# X13_Power_Distribution_D.net
KiCad netlist of a schematic drawn in EAGLE
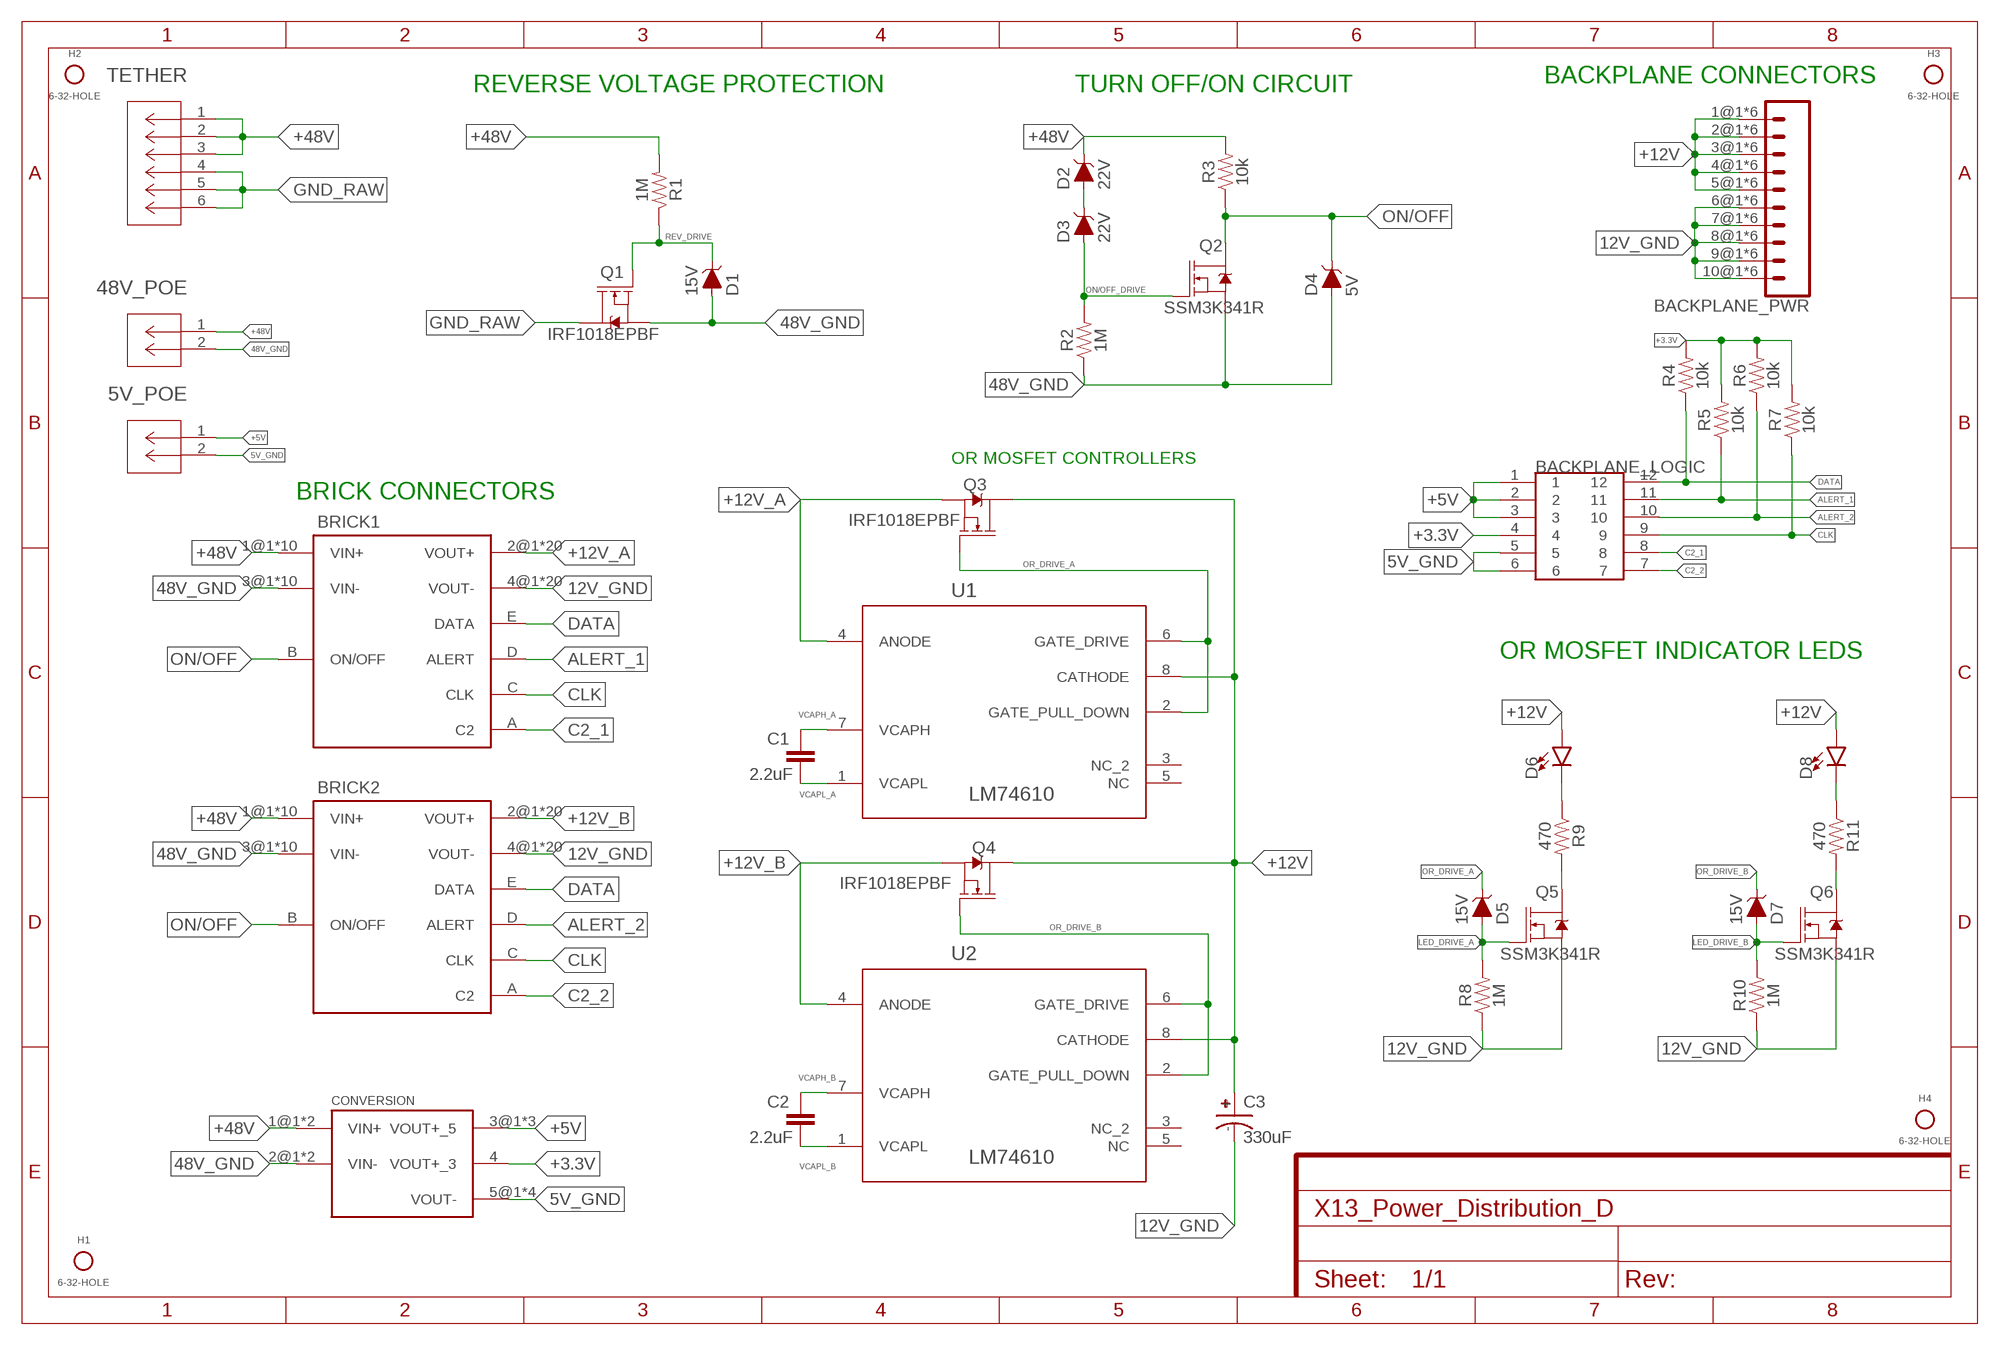
[diagram p0: schematic, sheet 1, part 1 of 2]
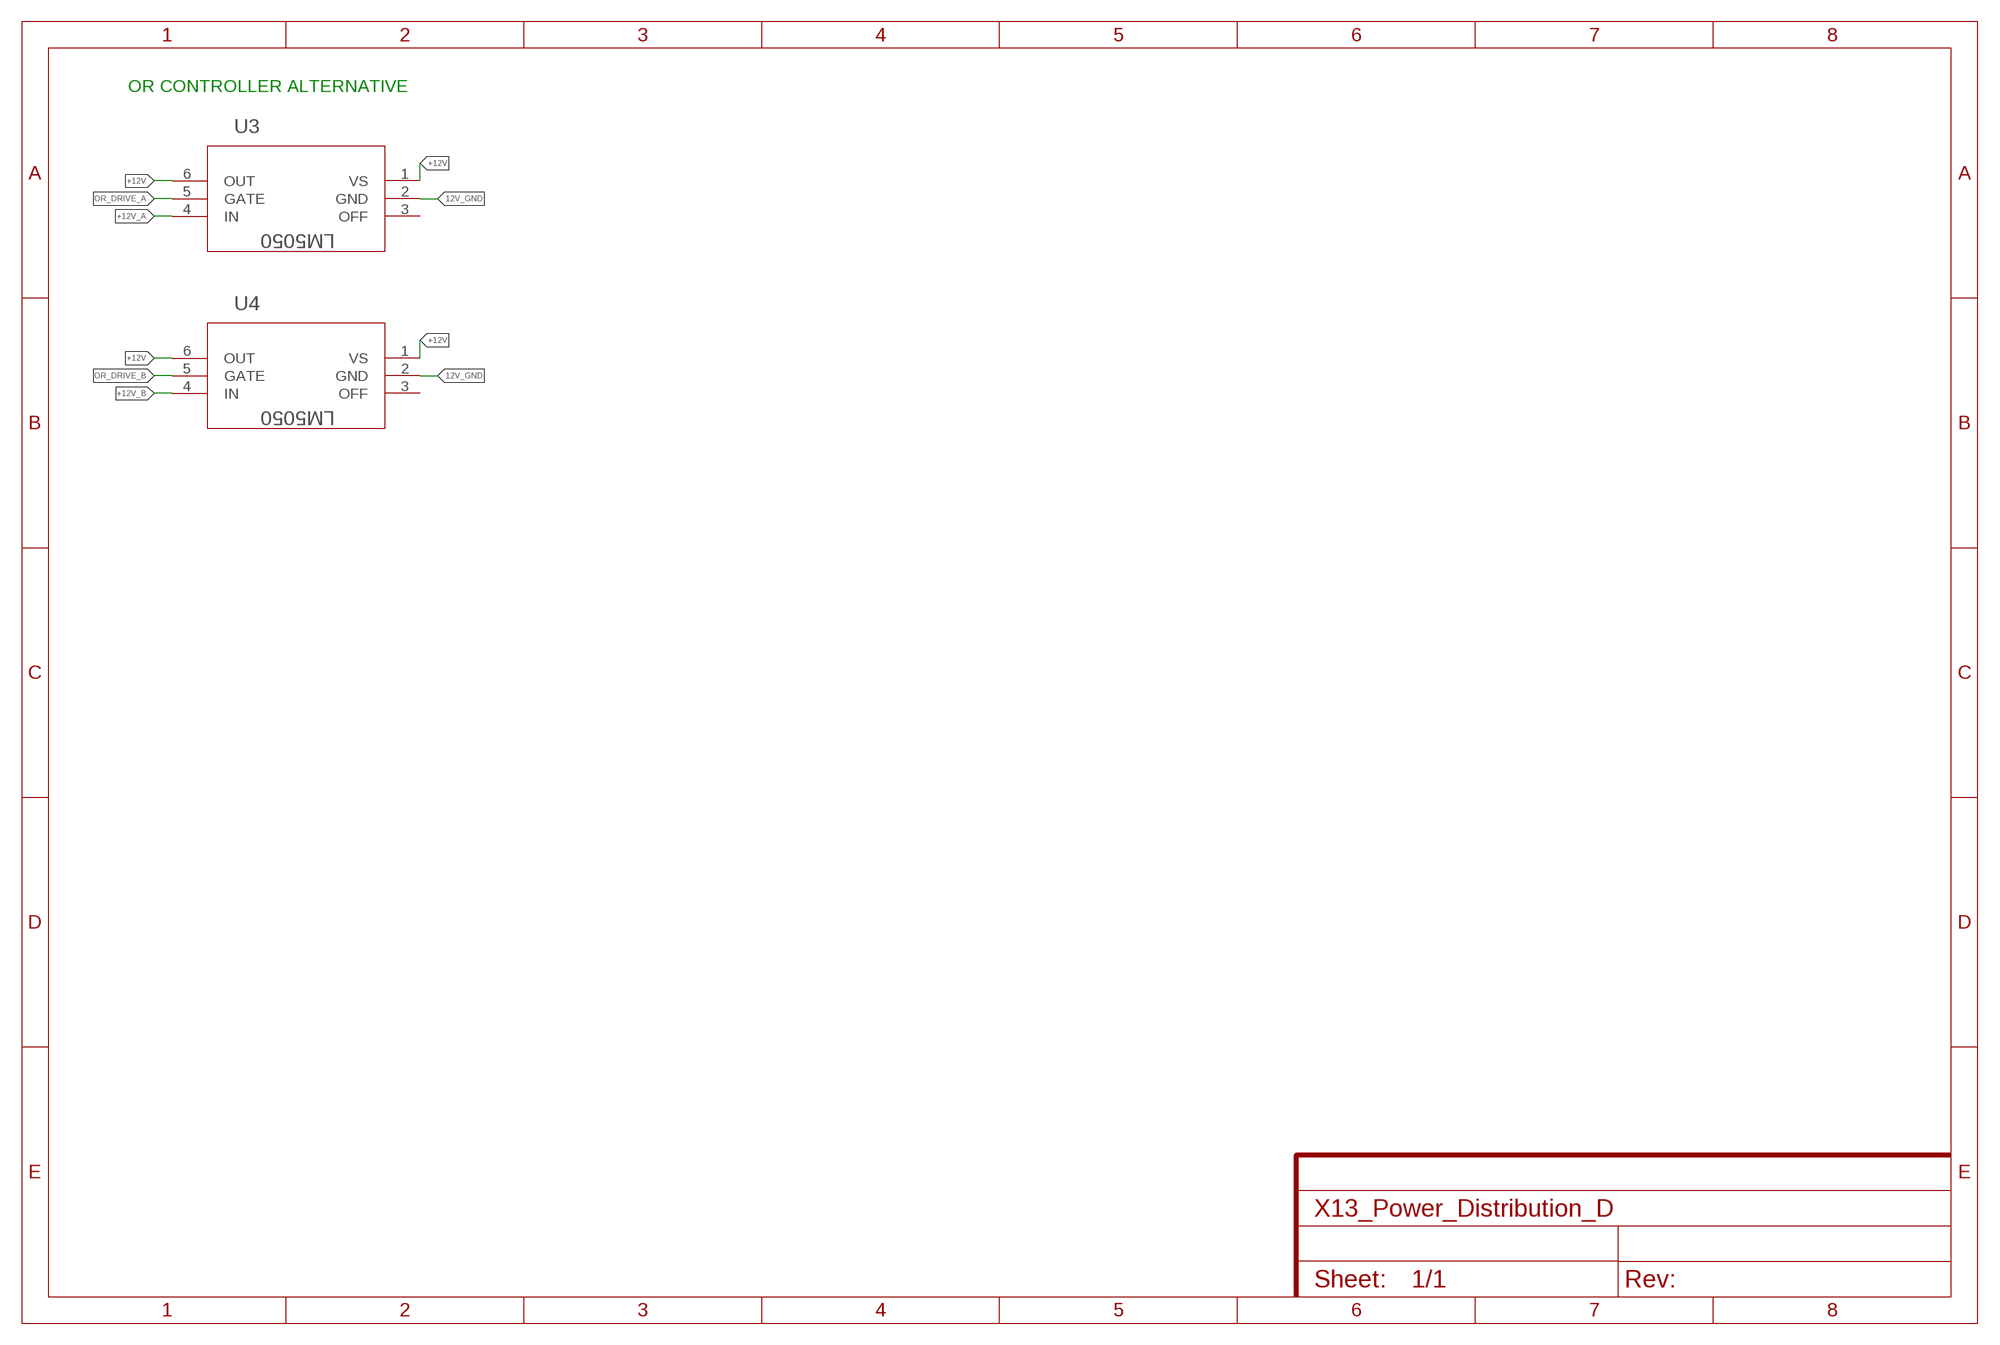
[diagram p1: schematic, sheet 1, part 2 of 2]

(export (version "E")
  (design (tool "Eeschema 10.0.6"))
  (components
    (comp (ref "5V_POE")
      (value "POE_TERMINAL")
      (footprint "eagle-import:CONN2_282834-2_TEC")
      (fields
        (field (name "MANUFACTURER_PART_NUMBER") "282834-2")
        (field (name "COPYRIGHT") "Copyright (C) 2016 Accelerated Designs. All rights reserved")
      )
      (libsource (lib "eagle-import") (part "POE_TERMINAL"))
    )
    (comp (ref "48V_POE")
      (value "POE_TERMINAL")
      (footprint "eagle-import:CONN2_282834-2_TEC")
      (fields
        (field (name "MANUFACTURER_PART_NUMBER") "282834-2")
        (field (name "COPYRIGHT") "Copyright (C) 2016 Accelerated Designs. All rights reserved")
      )
      (libsource (lib "eagle-import") (part "POE_TERMINAL"))
    )
    (comp (ref "BACKPLANE_LOGIC")
      (value "IPL1-106-01-L-D-K")
      (footprint "eagle-import:IPL1-106-01-L-D-K")
      (libsource (lib "eagle-import") (part "IPL1-106-01-L-D-K"))
    )
    (comp (ref "BACKPLANE_PWR")
      (value "MPPT-10-01-01-L-RA-SD")
      (footprint "eagle-import:MPPT-10-01-01-L-RA-SD")
      (libsource (lib "eagle-import") (part "MPPT-10-01-01-L-RA-SD"))
    )
    (comp (ref "BRICK1")
      (value "DIST2BRICKVER_D2")
      (footprint "eagle-import:DIST2BRICK_D2")
      (libsource (lib "eagle-import") (part "DIST2BRICKVER_D2"))
    )
    (comp (ref "BRICK2")
      (value "DIST2BRICKVER_D2")
      (footprint "eagle-import:DIST2BRICK_D2")
      (libsource (lib "eagle-import") (part "DIST2BRICKVER_D2"))
    )
    (comp (ref "C1")
      (value "2.2uF")
      (footprint "eagle-import:0603")
      (libsource (lib "eagle-import") (part "0.1UF-0603-100V-10%"))
    )
    (comp (ref "C2")
      (value "2.2uF")
      (footprint "eagle-import:0603")
      (libsource (lib "eagle-import") (part "0.1UF-0603-100V-10%"))
    )
    (comp (ref "C3")
      (value "330uF")
      (footprint "eagle-import:CAPAE1030X1050N")
      (fields
        (field (name "ARROW_PART_NUMBER") "UCM1H331MNL1GS")
        (field (name "MOUSER_PART_NUMBER") "647-UCM1H331MNL1GS")
      )
      (libsource (lib "eagle-import") (part "UCM1H331MNL1GS"))
    )
    (comp (ref "CONVERSION")
      (value "DIST2CON")
      (footprint "eagle-import:DIST2CON")
      (libsource (lib "eagle-import") (part "DIST2CON"))
    )
    (comp (ref "D1")
      (value "15V")
      (footprint "eagle-import:SOD-323")
      (libsource (lib "eagle-import") (part "DIODE-ZENER-BZT52C3V6S"))
    )
    (comp (ref "D2")
      (value "22V")
      (footprint "eagle-import:SOD-323")
      (libsource (lib "eagle-import") (part "DIODE-ZENER-BZT52C3V6S"))
    )
    (comp (ref "D3")
      (value "22V")
      (footprint "eagle-import:SOD-323")
      (libsource (lib "eagle-import") (part "DIODE-ZENER-BZT52C3V6S"))
    )
    (comp (ref "D4")
      (value "5V")
      (footprint "eagle-import:SOD-323")
      (libsource (lib "eagle-import") (part "DIODE-ZENER-BZT52C3V6S"))
    )
    (comp (ref "D5")
      (value "15V")
      (footprint "eagle-import:SOD-323")
      (libsource (lib "eagle-import") (part "DIODE-ZENER-BZT52C3V6S"))
    )
    (comp (ref "D6")
      (value "LED0603")
      (footprint "eagle-import:LED-0603")
      (libsource (lib "eagle-import") (part "LED0603"))
    )
    (comp (ref "D7")
      (value "15V")
      (footprint "eagle-import:SOD-323")
      (libsource (lib "eagle-import") (part "DIODE-ZENER-BZT52C3V6S"))
    )
    (comp (ref "D8")
      (value "LED0603")
      (footprint "eagle-import:LED-0603")
      (libsource (lib "eagle-import") (part "LED0603"))
    )
    (comp (ref "H1")
      (value "6-32-HOLE")
      (footprint "eagle-import:6-32-HOLE")
      (libsource (lib "eagle-import") (part "6-32-HOLE"))
    )
    (comp (ref "H2")
      (value "6-32-HOLE")
      (footprint "eagle-import:6-32-HOLE")
      (libsource (lib "eagle-import") (part "6-32-HOLE"))
    )
    (comp (ref "H3")
      (value "6-32-HOLE")
      (footprint "eagle-import:6-32-HOLE")
      (libsource (lib "eagle-import") (part "6-32-HOLE"))
    )
    (comp (ref "H4")
      (value "6-32-HOLE")
      (footprint "eagle-import:6-32-HOLE")
      (libsource (lib "eagle-import") (part "6-32-HOLE"))
    )
    (comp (ref "Q1")
      (value "IRF1018EPBF")
      (footprint "eagle-import:TO263")
      (libsource (lib "eagle-import") (part "IRF1018EPBF"))
    )
    (comp (ref "Q2")
      (value "SSM3K341R")
      (footprint "eagle-import:SOT323")
      (libsource (lib "eagle-import") (part "MOSFET-NCH-2N7002PW"))
    )
    (comp (ref "Q3")
      (value "IRF1018EPBF")
      (footprint "eagle-import:TO263")
      (libsource (lib "eagle-import") (part "IRF1018EPBF"))
    )
    (comp (ref "Q4")
      (value "IRF1018EPBF")
      (footprint "eagle-import:TO263")
      (libsource (lib "eagle-import") (part "IRF1018EPBF"))
    )
    (comp (ref "Q5")
      (value "SSM3K341R")
      (footprint "eagle-import:SOT323")
      (libsource (lib "eagle-import") (part "MOSFET-NCH-2N7002PW"))
    )
    (comp (ref "Q6")
      (value "SSM3K341R")
      (footprint "eagle-import:SOT323")
      (libsource (lib "eagle-import") (part "MOSFET-NCH-2N7002PW"))
    )
    (comp (ref "R1")
      (value "1M")
      (footprint "eagle-import:0603")
      (libsource (lib "eagle-import") (part "RESISTOR0603"))
    )
    (comp (ref "R2")
      (value "1M")
      (footprint "eagle-import:0603")
      (fields (field (name "SPICEPREFIX") "R"))
      (libsource (lib "eagle-import") (part "RESISTOR0603"))
    )
    (comp (ref "R3")
      (value "10k")
      (footprint "eagle-import:0603")
      (fields (field (name "SPICEPREFIX") "R"))
      (libsource (lib "eagle-import") (part "RESISTOR0603"))
    )
    (comp (ref "R4")
      (value "10k")
      (footprint "eagle-import:0603")
      (libsource (lib "eagle-import") (part "RESISTOR0603"))
    )
    (comp (ref "R5")
      (value "10k")
      (footprint "eagle-import:0603")
      (libsource (lib "eagle-import") (part "RESISTOR0603"))
    )
    (comp (ref "R6")
      (value "10k")
      (footprint "eagle-import:0603")
      (libsource (lib "eagle-import") (part "RESISTOR0603"))
    )
    (comp (ref "R7")
      (value "10k")
      (footprint "eagle-import:0603")
      (libsource (lib "eagle-import") (part "RESISTOR0603"))
    )
    (comp (ref "R8")
      (value "1M")
      (footprint "eagle-import:0603")
      (fields (field (name "SPICEPREFIX") "R"))
      (libsource (lib "eagle-import") (part "RESISTOR0603"))
    )
    (comp (ref "R9")
      (value "470")
      (footprint "eagle-import:0603")
      (libsource (lib "eagle-import") (part "RESISTOR0603"))
    )
    (comp (ref "R10")
      (value "1M")
      (footprint "eagle-import:0603")
      (fields (field (name "SPICEPREFIX") "R"))
      (libsource (lib "eagle-import") (part "RESISTOR0603"))
    )
    (comp (ref "R11")
      (value "470")
      (footprint "eagle-import:0603")
      (libsource (lib "eagle-import") (part "RESISTOR0603"))
    )
    (comp (ref "TETHER")
      (value "48V")
      (footprint "eagle-import:CON6_P5MM_VER_TERM-BLK_TYC")
      (fields (field (name "MANUFACTURER_PART_NUMBER") "796636-6"))
      (libsource (lib "eagle-import") (part "DIST_TO_TETHER"))
    )
    (comp (ref "U1")
      (value "LM74610")
      (footprint "eagle-import:DGK0008A_M")
      (fields (field (name "MANUFACTURER") "Texas Instruments") (field (name "PARTNUMBER") "LM74610QDGKRQ1"))
      (libsource (lib "eagle-import") (part "DIST_OR_DIODEDGK0008A_M"))
    )
    (comp (ref "U2")
      (value "LM74610")
      (footprint "eagle-import:DGK0008A_M")
      (fields (field (name "MANUFACTURER") "Texas Instruments") (field (name "PARTNUMBER") "LM74610QDGKRQ1"))
      (libsource (lib "eagle-import") (part "DIST_OR_DIODEDGK0008A_M"))
    )
    (comp (ref "U3")
      (value "LM5050")
      (footprint "eagle-import:MK06A-M")
      (fields
        (field (name "MANUFACTURER") "Texas Instruments")
        (field (name "MANUFACTURER_PART_NUMBER") "LM5050MK-1/NOPB")
      )
      (libsource (lib "eagle-import") (part "DIST_OR_CONTROL_ALTMK06A-M"))
    )
    (comp (ref "U4")
      (value "LM5050")
      (footprint "eagle-import:MK06A-M")
      (fields
        (field (name "MANUFACTURER") "Texas Instruments")
        (field (name "MANUFACTURER_PART_NUMBER") "LM5050MK-1/NOPB")
      )
      (libsource (lib "eagle-import") (part "DIST_OR_CONTROL_ALTMK06A-M"))
    )
  )
  (nets
    (net (code "1") (name "+3.3V") (class "Default")
      (node (ref "BACKPLANE_LOGIC") (pin "4") (pinfunction "4_4") (pintype "bidirectional"))
      (node (ref "CONVERSION") (pin "4") (pinfunction "VOUT+_3_4") (pintype "bidirectional"))
      (node (ref "R4") (pin "2") (pinfunction "2_2") (pintype "passive"))
      (node (ref "R5") (pin "2") (pinfunction "2_2") (pintype "passive"))
      (node (ref "R6") (pin "2") (pinfunction "2_2") (pintype "passive"))
      (node (ref "R7") (pin "2") (pinfunction "2_2") (pintype "passive"))
    )
    (net (code "2") (name "+5V") (class "Default")
      (node (ref "5V_POE") (pin "1") (pinfunction "1_1") (pintype "passive"))
      (node (ref "BACKPLANE_LOGIC") (pin "1") (pinfunction "1_1") (pintype "bidirectional"))
      (node (ref "BACKPLANE_LOGIC") (pin "2") (pinfunction "2_2") (pintype "bidirectional"))
      (node (ref "BACKPLANE_LOGIC") (pin "3") (pinfunction "3_3") (pintype "bidirectional"))
      (node (ref "CONVERSION") (pin "3@1") (pinfunction "VOUT+_5_3@1") (pintype "bidirectional"))
      (node (ref "CONVERSION") (pin "3@2") (pinfunction "VOUT+_5_3@2") (pintype "bidirectional"))
      (node (ref "CONVERSION") (pin "3@3") (pinfunction "VOUT+_5_3@3") (pintype "bidirectional"))
    )
    (net (code "3") (name "+12V") (class "Default")
      (node (ref "BACKPLANE_PWR") (pin "1@1") (pinfunction "1_1@1") (pintype "passive"))
      (node (ref "BACKPLANE_PWR") (pin "1@2") (pinfunction "1_1@2") (pintype "passive"))
      (node (ref "BACKPLANE_PWR") (pin "1@3") (pinfunction "1_1@3") (pintype "passive"))
      (node (ref "BACKPLANE_PWR") (pin "1@4") (pinfunction "1_1@4") (pintype "passive"))
      (node (ref "BACKPLANE_PWR") (pin "1@5") (pinfunction "1_1@5") (pintype "passive"))
      (node (ref "BACKPLANE_PWR") (pin "1@6") (pinfunction "1_1@6") (pintype "passive"))
      (node (ref "BACKPLANE_PWR") (pin "2@1") (pinfunction "2_2@1") (pintype "passive"))
      (node (ref "BACKPLANE_PWR") (pin "2@2") (pinfunction "2_2@2") (pintype "passive"))
      (node (ref "BACKPLANE_PWR") (pin "2@3") (pinfunction "2_2@3") (pintype "passive"))
      (node (ref "BACKPLANE_PWR") (pin "2@4") (pinfunction "2_2@4") (pintype "passive"))
      (node (ref "BACKPLANE_PWR") (pin "2@5") (pinfunction "2_2@5") (pintype "passive"))
      (node (ref "BACKPLANE_PWR") (pin "2@6") (pinfunction "2_2@6") (pintype "passive"))
      (node (ref "BACKPLANE_PWR") (pin "3@1") (pinfunction "3_3@1") (pintype "passive"))
      (node (ref "BACKPLANE_PWR") (pin "3@2") (pinfunction "3_3@2") (pintype "passive"))
      (node (ref "BACKPLANE_PWR") (pin "3@3") (pinfunction "3_3@3") (pintype "passive"))
      (node (ref "BACKPLANE_PWR") (pin "3@4") (pinfunction "3_3@4") (pintype "passive"))
      (node (ref "BACKPLANE_PWR") (pin "3@5") (pinfunction "3_3@5") (pintype "passive"))
      (node (ref "BACKPLANE_PWR") (pin "3@6") (pinfunction "3_3@6") (pintype "passive"))
      (node (ref "BACKPLANE_PWR") (pin "4@1") (pinfunction "4_4@1") (pintype "passive"))
      (node (ref "BACKPLANE_PWR") (pin "4@2") (pinfunction "4_4@2") (pintype "passive"))
      (node (ref "BACKPLANE_PWR") (pin "4@3") (pinfunction "4_4@3") (pintype "passive"))
      (node (ref "BACKPLANE_PWR") (pin "4@4") (pinfunction "4_4@4") (pintype "passive"))
      (node (ref "BACKPLANE_PWR") (pin "4@5") (pinfunction "4_4@5") (pintype "passive"))
      (node (ref "BACKPLANE_PWR") (pin "4@6") (pinfunction "4_4@6") (pintype "passive"))
      (node (ref "BACKPLANE_PWR") (pin "5@1") (pinfunction "5_5@1") (pintype "passive"))
      (node (ref "BACKPLANE_PWR") (pin "5@2") (pinfunction "5_5@2") (pintype "passive"))
      (node (ref "BACKPLANE_PWR") (pin "5@3") (pinfunction "5_5@3") (pintype "passive"))
      (node (ref "BACKPLANE_PWR") (pin "5@4") (pinfunction "5_5@4") (pintype "passive"))
      (node (ref "BACKPLANE_PWR") (pin "5@5") (pinfunction "5_5@5") (pintype "passive"))
      (node (ref "BACKPLANE_PWR") (pin "5@6") (pinfunction "5_5@6") (pintype "passive"))
      (node (ref "C3") (pin "+") (pinfunction "+_+") (pintype "bidirectional"))
      (node (ref "D6") (pin "A") (pinfunction "A_A") (pintype "passive"))
      (node (ref "D8") (pin "A") (pinfunction "A_A") (pintype "passive"))
      (node (ref "Q3") (pin "3") (pinfunction "D_3") (pintype "bidirectional"))
      (node (ref "Q4") (pin "3") (pinfunction "D_3") (pintype "bidirectional"))
      (node (ref "U1") (pin "8") (pinfunction "CATHODE_8") (pintype "output"))
      (node (ref "U2") (pin "8") (pinfunction "CATHODE_8") (pintype "output"))
      (node (ref "U3") (pin "1") (pinfunction "VS_1") (pintype "passive"))
      (node (ref "U3") (pin "6") (pinfunction "OUT_6") (pintype "output"))
      (node (ref "U4") (pin "1") (pinfunction "VS_1") (pintype "passive"))
      (node (ref "U4") (pin "6") (pinfunction "OUT_6") (pintype "output"))
    )
    (net (code "4") (name "+12V_A") (class "Default")
      (node (ref "BRICK1") (pin "2@1") (pinfunction "VOUT+_2@1") (pintype "bidirectional"))
      (node (ref "BRICK1") (pin "2@10") (pinfunction "VOUT+_2@10") (pintype "bidirectional"))
      (node (ref "BRICK1") (pin "2@11") (pinfunction "VOUT+_2@11") (pintype "bidirectional"))
      (node (ref "BRICK1") (pin "2@12") (pinfunction "VOUT+_2@12") (pintype "bidirectional"))
      (node (ref "BRICK1") (pin "2@13") (pinfunction "VOUT+_2@13") (pintype "bidirectional"))
      (node (ref "BRICK1") (pin "2@14") (pinfunction "VOUT+_2@14") (pintype "bidirectional"))
      (node (ref "BRICK1") (pin "2@15") (pinfunction "VOUT+_2@15") (pintype "bidirectional"))
      (node (ref "BRICK1") (pin "2@16") (pinfunction "VOUT+_2@16") (pintype "bidirectional"))
      (node (ref "BRICK1") (pin "2@17") (pinfunction "VOUT+_2@17") (pintype "bidirectional"))
      (node (ref "BRICK1") (pin "2@18") (pinfunction "VOUT+_2@18") (pintype "bidirectional"))
      (node (ref "BRICK1") (pin "2@19") (pinfunction "VOUT+_2@19") (pintype "bidirectional"))
      (node (ref "BRICK1") (pin "2@2") (pinfunction "VOUT+_2@2") (pintype "bidirectional"))
      (node (ref "BRICK1") (pin "2@20") (pinfunction "VOUT+_2@20") (pintype "bidirectional"))
      (node (ref "BRICK1") (pin "2@3") (pinfunction "VOUT+_2@3") (pintype "bidirectional"))
      (node (ref "BRICK1") (pin "2@4") (pinfunction "VOUT+_2@4") (pintype "bidirectional"))
      (node (ref "BRICK1") (pin "2@5") (pinfunction "VOUT+_2@5") (pintype "bidirectional"))
      (node (ref "BRICK1") (pin "2@6") (pinfunction "VOUT+_2@6") (pintype "bidirectional"))
      (node (ref "BRICK1") (pin "2@7") (pinfunction "VOUT+_2@7") (pintype "bidirectional"))
      (node (ref "BRICK1") (pin "2@8") (pinfunction "VOUT+_2@8") (pintype "bidirectional"))
      (node (ref "BRICK1") (pin "2@9") (pinfunction "VOUT+_2@9") (pintype "bidirectional"))
      (node (ref "Q3") (pin "2") (pinfunction "S_2") (pintype "bidirectional"))
      (node (ref "U1") (pin "4") (pinfunction "ANODE_4") (pintype "power_in"))
      (node (ref "U3") (pin "4") (pinfunction "IN_4") (pintype "input"))
    )
    (net (code "5") (name "+12V_B") (class "Default")
      (node (ref "BRICK2") (pin "2@1") (pinfunction "VOUT+_2@1") (pintype "bidirectional"))
      (node (ref "BRICK2") (pin "2@10") (pinfunction "VOUT+_2@10") (pintype "bidirectional"))
      (node (ref "BRICK2") (pin "2@11") (pinfunction "VOUT+_2@11") (pintype "bidirectional"))
      (node (ref "BRICK2") (pin "2@12") (pinfunction "VOUT+_2@12") (pintype "bidirectional"))
      (node (ref "BRICK2") (pin "2@13") (pinfunction "VOUT+_2@13") (pintype "bidirectional"))
      (node (ref "BRICK2") (pin "2@14") (pinfunction "VOUT+_2@14") (pintype "bidirectional"))
      (node (ref "BRICK2") (pin "2@15") (pinfunction "VOUT+_2@15") (pintype "bidirectional"))
      (node (ref "BRICK2") (pin "2@16") (pinfunction "VOUT+_2@16") (pintype "bidirectional"))
      (node (ref "BRICK2") (pin "2@17") (pinfunction "VOUT+_2@17") (pintype "bidirectional"))
      (node (ref "BRICK2") (pin "2@18") (pinfunction "VOUT+_2@18") (pintype "bidirectional"))
      (node (ref "BRICK2") (pin "2@19") (pinfunction "VOUT+_2@19") (pintype "bidirectional"))
      (node (ref "BRICK2") (pin "2@2") (pinfunction "VOUT+_2@2") (pintype "bidirectional"))
      (node (ref "BRICK2") (pin "2@20") (pinfunction "VOUT+_2@20") (pintype "bidirectional"))
      (node (ref "BRICK2") (pin "2@3") (pinfunction "VOUT+_2@3") (pintype "bidirectional"))
      (node (ref "BRICK2") (pin "2@4") (pinfunction "VOUT+_2@4") (pintype "bidirectional"))
      (node (ref "BRICK2") (pin "2@5") (pinfunction "VOUT+_2@5") (pintype "bidirectional"))
      (node (ref "BRICK2") (pin "2@6") (pinfunction "VOUT+_2@6") (pintype "bidirectional"))
      (node (ref "BRICK2") (pin "2@7") (pinfunction "VOUT+_2@7") (pintype "bidirectional"))
      (node (ref "BRICK2") (pin "2@8") (pinfunction "VOUT+_2@8") (pintype "bidirectional"))
      (node (ref "BRICK2") (pin "2@9") (pinfunction "VOUT+_2@9") (pintype "bidirectional"))
      (node (ref "Q4") (pin "2") (pinfunction "S_2") (pintype "bidirectional"))
      (node (ref "U2") (pin "4") (pinfunction "ANODE_4") (pintype "power_in"))
      (node (ref "U4") (pin "4") (pinfunction "IN_4") (pintype "input"))
    )
    (net (code "6") (name "+48V") (class "Default")
      (node (ref "48V_POE") (pin "1") (pinfunction "1_1") (pintype "passive"))
      (node (ref "BRICK1") (pin "1@1") (pinfunction "VIN+_1@1") (pintype "bidirectional"))
      (node (ref "BRICK1") (pin "1@10") (pinfunction "VIN+_1@10") (pintype "bidirectional"))
      (node (ref "BRICK1") (pin "1@2") (pinfunction "VIN+_1@2") (pintype "bidirectional"))
      (node (ref "BRICK1") (pin "1@3") (pinfunction "VIN+_1@3") (pintype "bidirectional"))
      (node (ref "BRICK1") (pin "1@4") (pinfunction "VIN+_1@4") (pintype "bidirectional"))
      (node (ref "BRICK1") (pin "1@5") (pinfunction "VIN+_1@5") (pintype "bidirectional"))
      (node (ref "BRICK1") (pin "1@6") (pinfunction "VIN+_1@6") (pintype "bidirectional"))
      (node (ref "BRICK1") (pin "1@7") (pinfunction "VIN+_1@7") (pintype "bidirectional"))
      (node (ref "BRICK1") (pin "1@8") (pinfunction "VIN+_1@8") (pintype "bidirectional"))
      (node (ref "BRICK1") (pin "1@9") (pinfunction "VIN+_1@9") (pintype "bidirectional"))
      (node (ref "BRICK2") (pin "1@1") (pinfunction "VIN+_1@1") (pintype "bidirectional"))
      (node (ref "BRICK2") (pin "1@10") (pinfunction "VIN+_1@10") (pintype "bidirectional"))
      (node (ref "BRICK2") (pin "1@2") (pinfunction "VIN+_1@2") (pintype "bidirectional"))
      (node (ref "BRICK2") (pin "1@3") (pinfunction "VIN+_1@3") (pintype "bidirectional"))
      (node (ref "BRICK2") (pin "1@4") (pinfunction "VIN+_1@4") (pintype "bidirectional"))
      (node (ref "BRICK2") (pin "1@5") (pinfunction "VIN+_1@5") (pintype "bidirectional"))
      (node (ref "BRICK2") (pin "1@6") (pinfunction "VIN+_1@6") (pintype "bidirectional"))
      (node (ref "BRICK2") (pin "1@7") (pinfunction "VIN+_1@7") (pintype "bidirectional"))
      (node (ref "BRICK2") (pin "1@8") (pinfunction "VIN+_1@8") (pintype "bidirectional"))
      (node (ref "BRICK2") (pin "1@9") (pinfunction "VIN+_1@9") (pintype "bidirectional"))
      (node (ref "CONVERSION") (pin "1@1") (pinfunction "VIN+_1@1") (pintype "bidirectional"))
      (node (ref "CONVERSION") (pin "1@2") (pinfunction "VIN+_1@2") (pintype "bidirectional"))
      (node (ref "D2") (pin "C") (pinfunction "C_C") (pintype "passive"))
      (node (ref "R1") (pin "2") (pinfunction "2_2") (pintype "passive"))
      (node (ref "R3") (pin "2") (pinfunction "2_2") (pintype "passive"))
      (node (ref "TETHER") (pin "1") (pinfunction "1_1") (pintype "passive"))
      (node (ref "TETHER") (pin "2") (pinfunction "2_2") (pintype "passive"))
      (node (ref "TETHER") (pin "3") (pinfunction "3_3") (pintype "passive"))
    )
    (net (code "7") (name "/ON{slash}OFF_DRIVE") (class "Default")
      (node (ref "D3") (pin "A") (pinfunction "A_A") (pintype "passive"))
      (node (ref "Q2") (pin "1") (pinfunction "G_1") (pintype "bidirectional"))
      (node (ref "R2") (pin "2") (pinfunction "2_2") (pintype "passive"))
    )
    (net (code "8") (name "/REV_DRIVE") (class "Default")
      (node (ref "D1") (pin "C") (pinfunction "C_C") (pintype "passive"))
      (node (ref "Q1") (pin "1") (pinfunction "G_1") (pintype "bidirectional"))
      (node (ref "R1") (pin "1") (pinfunction "1_1") (pintype "passive"))
    )
    (net (code "9") (name "/VCAPH_A") (class "Default")
      (node (ref "C1") (pin "1") (pinfunction "1_1") (pintype "passive"))
      (node (ref "U1") (pin "7") (pinfunction "VCAPH_7") (pintype "passive"))
    )
    (net (code "10") (name "/VCAPH_B") (class "Default")
      (node (ref "C2") (pin "1") (pinfunction "1_1") (pintype "passive"))
      (node (ref "U2") (pin "7") (pinfunction "VCAPH_7") (pintype "passive"))
    )
    (net (code "11") (name "/VCAPL_A") (class "Default")
      (node (ref "C1") (pin "2") (pinfunction "2_2") (pintype "passive"))
      (node (ref "U1") (pin "1") (pinfunction "VCAPL_1") (pintype "passive"))
    )
    (net (code "12") (name "/VCAPL_B") (class "Default")
      (node (ref "C2") (pin "2") (pinfunction "2_2") (pintype "passive"))
      (node (ref "U2") (pin "1") (pinfunction "VCAPL_1") (pintype "passive"))
    )
    (net (code "13") (name "5V_GND") (class "Default")
      (node (ref "5V_POE") (pin "2") (pinfunction "2_2") (pintype "passive"))
      (node (ref "BACKPLANE_LOGIC") (pin "5") (pinfunction "5_5") (pintype "bidirectional"))
      (node (ref "BACKPLANE_LOGIC") (pin "6") (pinfunction "6_6") (pintype "bidirectional"))
      (node (ref "CONVERSION") (pin "5@1") (pinfunction "VOUT-_5@1") (pintype "bidirectional"))
      (node (ref "CONVERSION") (pin "5@2") (pinfunction "VOUT-_5@2") (pintype "bidirectional"))
      (node (ref "CONVERSION") (pin "5@3") (pinfunction "VOUT-_5@3") (pintype "bidirectional"))
      (node (ref "CONVERSION") (pin "5@4") (pinfunction "VOUT-_5@4") (pintype "bidirectional"))
    )
    (net (code "14") (name "12V_GND") (class "Default")
      (node (ref "BACKPLANE_PWR") (pin "10@1") (pinfunction "10_10@1") (pintype "passive"))
      (node (ref "BACKPLANE_PWR") (pin "10@2") (pinfunction "10_10@2") (pintype "passive"))
      (node (ref "BACKPLANE_PWR") (pin "10@3") (pinfunction "10_10@3") (pintype "passive"))
      (node (ref "BACKPLANE_PWR") (pin "10@4") (pinfunction "10_10@4") (pintype "passive"))
      (node (ref "BACKPLANE_PWR") (pin "10@5") (pinfunction "10_10@5") (pintype "passive"))
      (node (ref "BACKPLANE_PWR") (pin "10@6") (pinfunction "10_10@6") (pintype "passive"))
      (node (ref "BACKPLANE_PWR") (pin "6@1") (pinfunction "6_6@1") (pintype "passive"))
      (node (ref "BACKPLANE_PWR") (pin "6@2") (pinfunction "6_6@2") (pintype "passive"))
      (node (ref "BACKPLANE_PWR") (pin "6@3") (pinfunction "6_6@3") (pintype "passive"))
      (node (ref "BACKPLANE_PWR") (pin "6@4") (pinfunction "6_6@4") (pintype "passive"))
      (node (ref "BACKPLANE_PWR") (pin "6@5") (pinfunction "6_6@5") (pintype "passive"))
      (node (ref "BACKPLANE_PWR") (pin "6@6") (pinfunction "6_6@6") (pintype "passive"))
      (node (ref "BACKPLANE_PWR") (pin "7@1") (pinfunction "7_7@1") (pintype "passive"))
      (node (ref "BACKPLANE_PWR") (pin "7@2") (pinfunction "7_7@2") (pintype "passive"))
      (node (ref "BACKPLANE_PWR") (pin "7@3") (pinfunction "7_7@3") (pintype "passive"))
      (node (ref "BACKPLANE_PWR") (pin "7@4") (pinfunction "7_7@4") (pintype "passive"))
      (node (ref "BACKPLANE_PWR") (pin "7@5") (pinfunction "7_7@5") (pintype "passive"))
      (node (ref "BACKPLANE_PWR") (pin "7@6") (pinfunction "7_7@6") (pintype "passive"))
      (node (ref "BACKPLANE_PWR") (pin "8@1") (pinfunction "8_8@1") (pintype "passive"))
      (node (ref "BACKPLANE_PWR") (pin "8@2") (pinfunction "8_8@2") (pintype "passive"))
      (node (ref "BACKPLANE_PWR") (pin "8@3") (pinfunction "8_8@3") (pintype "passive"))
      (node (ref "BACKPLANE_PWR") (pin "8@4") (pinfunction "8_8@4") (pintype "passive"))
      (node (ref "BACKPLANE_PWR") (pin "8@5") (pinfunction "8_8@5") (pintype "passive"))
      (node (ref "BACKPLANE_PWR") (pin "8@6") (pinfunction "8_8@6") (pintype "passive"))
      (node (ref "BACKPLANE_PWR") (pin "9@1") (pinfunction "9_9@1") (pintype "passive"))
      (node (ref "BACKPLANE_PWR") (pin "9@2") (pinfunction "9_9@2") (pintype "passive"))
      (node (ref "BACKPLANE_PWR") (pin "9@3") (pinfunction "9_9@3") (pintype "passive"))
      (node (ref "BACKPLANE_PWR") (pin "9@4") (pinfunction "9_9@4") (pintype "passive"))
      (node (ref "BACKPLANE_PWR") (pin "9@5") (pinfunction "9_9@5") (pintype "passive"))
      (node (ref "BACKPLANE_PWR") (pin "9@6") (pinfunction "9_9@6") (pintype "passive"))
      (node (ref "BRICK1") (pin "4@1") (pinfunction "VOUT-_4@1") (pintype "bidirectional"))
      (node (ref "BRICK1") (pin "4@10") (pinfunction "VOUT-_4@10") (pintype "bidirectional"))
      (node (ref "BRICK1") (pin "4@11") (pinfunction "VOUT-_4@11") (pintype "bidirectional"))
      (node (ref "BRICK1") (pin "4@12") (pinfunction "VOUT-_4@12") (pintype "bidirectional"))
      (node (ref "BRICK1") (pin "4@13") (pinfunction "VOUT-_4@13") (pintype "bidirectional"))
      (node (ref "BRICK1") (pin "4@14") (pinfunction "VOUT-_4@14") (pintype "bidirectional"))
      (node (ref "BRICK1") (pin "4@15") (pinfunction "VOUT-_4@15") (pintype "bidirectional"))
      (node (ref "BRICK1") (pin "4@16") (pinfunction "VOUT-_4@16") (pintype "bidirectional"))
      (node (ref "BRICK1") (pin "4@17") (pinfunction "VOUT-_4@17") (pintype "bidirectional"))
      (node (ref "BRICK1") (pin "4@18") (pinfunction "VOUT-_4@18") (pintype "bidirectional"))
      (node (ref "BRICK1") (pin "4@19") (pinfunction "VOUT-_4@19") (pintype "bidirectional"))
      (node (ref "BRICK1") (pin "4@2") (pinfunction "VOUT-_4@2") (pintype "bidirectional"))
      (node (ref "BRICK1") (pin "4@20") (pinfunction "VOUT-_4@20") (pintype "bidirectional"))
      (node (ref "BRICK1") (pin "4@3") (pinfunction "VOUT-_4@3") (pintype "bidirectional"))
      (node (ref "BRICK1") (pin "4@4") (pinfunction "VOUT-_4@4") (pintype "bidirectional"))
      (node (ref "BRICK1") (pin "4@5") (pinfunction "VOUT-_4@5") (pintype "bidirectional"))
      (node (ref "BRICK1") (pin "4@6") (pinfunction "VOUT-_4@6") (pintype "bidirectional"))
      (node (ref "BRICK1") (pin "4@7") (pinfunction "VOUT-_4@7") (pintype "bidirectional"))
      (node (ref "BRICK1") (pin "4@8") (pinfunction "VOUT-_4@8") (pintype "bidirectional"))
      (node (ref "BRICK1") (pin "4@9") (pinfunction "VOUT-_4@9") (pintype "bidirectional"))
      (node (ref "BRICK2") (pin "4@1") (pinfunction "VOUT-_4@1") (pintype "bidirectional"))
      (node (ref "BRICK2") (pin "4@10") (pinfunction "VOUT-_4@10") (pintype "bidirectional"))
      (node (ref "BRICK2") (pin "4@11") (pinfunction "VOUT-_4@11") (pintype "bidirectional"))
      (node (ref "BRICK2") (pin "4@12") (pinfunction "VOUT-_4@12") (pintype "bidirectional"))
      (node (ref "BRICK2") (pin "4@13") (pinfunction "VOUT-_4@13") (pintype "bidirectional"))
      (node (ref "BRICK2") (pin "4@14") (pinfunction "VOUT-_4@14") (pintype "bidirectional"))
      (node (ref "BRICK2") (pin "4@15") (pinfunction "VOUT-_4@15") (pintype "bidirectional"))
      (node (ref "BRICK2") (pin "4@16") (pinfunction "VOUT-_4@16") (pintype "bidirectional"))
      (node (ref "BRICK2") (pin "4@17") (pinfunction "VOUT-_4@17") (pintype "bidirectional"))
      (node (ref "BRICK2") (pin "4@18") (pinfunction "VOUT-_4@18") (pintype "bidirectional"))
      (node (ref "BRICK2") (pin "4@19") (pinfunction "VOUT-_4@19") (pintype "bidirectional"))
      (node (ref "BRICK2") (pin "4@2") (pinfunction "VOUT-_4@2") (pintype "bidirectional"))
      (node (ref "BRICK2") (pin "4@20") (pinfunction "VOUT-_4@20") (pintype "bidirectional"))
      (node (ref "BRICK2") (pin "4@3") (pinfunction "VOUT-_4@3") (pintype "bidirectional"))
      (node (ref "BRICK2") (pin "4@4") (pinfunction "VOUT-_4@4") (pintype "bidirectional"))
      (node (ref "BRICK2") (pin "4@5") (pinfunction "VOUT-_4@5") (pintype "bidirectional"))
      (node (ref "BRICK2") (pin "4@6") (pinfunction "VOUT-_4@6") (pintype "bidirectional"))
      (node (ref "BRICK2") (pin "4@7") (pinfunction "VOUT-_4@7") (pintype "bidirectional"))
      (node (ref "BRICK2") (pin "4@8") (pinfunction "VOUT-_4@8") (pintype "bidirectional"))
      (node (ref "BRICK2") (pin "4@9") (pinfunction "VOUT-_4@9") (pintype "bidirectional"))
      (node (ref "C3") (pin "-") (pinfunction "-_-") (pintype "bidirectional"))
      (node (ref "Q5") (pin "2") (pinfunction "S_2") (pintype "bidirectional"))
      (node (ref "Q6") (pin "2") (pinfunction "S_2") (pintype "bidirectional"))
      (node (ref "R10") (pin "1") (pinfunction "1_1") (pintype "passive"))
      (node (ref "R8") (pin "1") (pinfunction "1_1") (pintype "passive"))
      (node (ref "U3") (pin "2") (pinfunction "GND_2") (pintype "power_in"))
      (node (ref "U4") (pin "2") (pinfunction "GND_2") (pintype "power_in"))
    )
    (net (code "15") (name "48V_GND") (class "Default")
      (node (ref "48V_POE") (pin "2") (pinfunction "2_2") (pintype "passive"))
      (node (ref "BRICK1") (pin "3@1") (pinfunction "VIN-_3@1") (pintype "bidirectional"))
      (node (ref "BRICK1") (pin "3@10") (pinfunction "VIN-_3@10") (pintype "bidirectional"))
      (node (ref "BRICK1") (pin "3@2") (pinfunction "VIN-_3@2") (pintype "bidirectional"))
      (node (ref "BRICK1") (pin "3@3") (pinfunction "VIN-_3@3") (pintype "bidirectional"))
      (node (ref "BRICK1") (pin "3@4") (pinfunction "VIN-_3@4") (pintype "bidirectional"))
      (node (ref "BRICK1") (pin "3@5") (pinfunction "VIN-_3@5") (pintype "bidirectional"))
      (node (ref "BRICK1") (pin "3@6") (pinfunction "VIN-_3@6") (pintype "bidirectional"))
      (node (ref "BRICK1") (pin "3@7") (pinfunction "VIN-_3@7") (pintype "bidirectional"))
      (node (ref "BRICK1") (pin "3@8") (pinfunction "VIN-_3@8") (pintype "bidirectional"))
      (node (ref "BRICK1") (pin "3@9") (pinfunction "VIN-_3@9") (pintype "bidirectional"))
      (node (ref "BRICK2") (pin "3@1") (pinfunction "VIN-_3@1") (pintype "bidirectional"))
      (node (ref "BRICK2") (pin "3@10") (pinfunction "VIN-_3@10") (pintype "bidirectional"))
      (node (ref "BRICK2") (pin "3@2") (pinfunction "VIN-_3@2") (pintype "bidirectional"))
      (node (ref "BRICK2") (pin "3@3") (pinfunction "VIN-_3@3") (pintype "bidirectional"))
      (node (ref "BRICK2") (pin "3@4") (pinfunction "VIN-_3@4") (pintype "bidirectional"))
      (node (ref "BRICK2") (pin "3@5") (pinfunction "VIN-_3@5") (pintype "bidirectional"))
      (node (ref "BRICK2") (pin "3@6") (pinfunction "VIN-_3@6") (pintype "bidirectional"))
      (node (ref "BRICK2") (pin "3@7") (pinfunction "VIN-_3@7") (pintype "bidirectional"))
      (node (ref "BRICK2") (pin "3@8") (pinfunction "VIN-_3@8") (pintype "bidirectional"))
      (node (ref "BRICK2") (pin "3@9") (pinfunction "VIN-_3@9") (pintype "bidirectional"))
      (node (ref "CONVERSION") (pin "2@1") (pinfunction "VIN-_2@1") (pintype "bidirectional"))
      (node (ref "CONVERSION") (pin "2@2") (pinfunction "VIN-_2@2") (pintype "bidirectional"))
      (node (ref "D1") (pin "A") (pinfunction "A_A") (pintype "passive"))
      (node (ref "D4") (pin "A") (pinfunction "A_A") (pintype "passive"))
      (node (ref "Q1") (pin "2") (pinfunction "S_2") (pintype "bidirectional"))
      (node (ref "Q2") (pin "2") (pinfunction "S_2") (pintype "bidirectional"))
      (node (ref "R2") (pin "1") (pinfunction "1_1") (pintype "passive"))
    )
    (net (code "16") (name "ALERT_1") (class "Default")
      (node (ref "BACKPLANE_LOGIC") (pin "11") (pinfunction "11_11") (pintype "bidirectional"))
      (node (ref "BRICK1") (pin "D") (pinfunction "ALERT_D") (pintype "bidirectional"))
      (node (ref "R5") (pin "1") (pinfunction "1_1") (pintype "passive"))
    )
    (net (code "17") (name "ALERT_2") (class "Default")
      (node (ref "BACKPLANE_LOGIC") (pin "10") (pinfunction "10_10") (pintype "bidirectional"))
      (node (ref "BRICK2") (pin "D") (pinfunction "ALERT_D") (pintype "bidirectional"))
      (node (ref "R6") (pin "1") (pinfunction "1_1") (pintype "passive"))
    )
    (net (code "18") (name "C2_1") (class "Default")
      (node (ref "BACKPLANE_LOGIC") (pin "8") (pinfunction "8_8") (pintype "bidirectional"))
      (node (ref "BRICK1") (pin "A") (pinfunction "C2_A") (pintype "bidirectional"))
    )
    (net (code "19") (name "C2_2") (class "Default")
      (node (ref "BACKPLANE_LOGIC") (pin "7") (pinfunction "7_7") (pintype "bidirectional"))
      (node (ref "BRICK2") (pin "A") (pinfunction "C2_A") (pintype "bidirectional"))
    )
    (net (code "20") (name "CLK") (class "Default")
      (node (ref "BACKPLANE_LOGIC") (pin "9") (pinfunction "9_9") (pintype "bidirectional"))
      (node (ref "BRICK1") (pin "C") (pinfunction "CLK_C") (pintype "bidirectional"))
      (node (ref "BRICK2") (pin "C") (pinfunction "CLK_C") (pintype "bidirectional"))
      (node (ref "R7") (pin "1") (pinfunction "1_1") (pintype "passive"))
    )
    (net (code "21") (name "DATA") (class "Default")
      (node (ref "BACKPLANE_LOGIC") (pin "12") (pinfunction "12_12") (pintype "bidirectional"))
      (node (ref "BRICK1") (pin "E") (pinfunction "DATA_E") (pintype "bidirectional"))
      (node (ref "BRICK2") (pin "E") (pinfunction "DATA_E") (pintype "bidirectional"))
      (node (ref "R4") (pin "1") (pinfunction "1_1") (pintype "passive"))
    )
    (net (code "22") (name "GND_RAW") (class "Default")
      (node (ref "Q1") (pin "3") (pinfunction "D_3") (pintype "bidirectional"))
      (node (ref "TETHER") (pin "4") (pinfunction "4_4") (pintype "passive"))
      (node (ref "TETHER") (pin "5") (pinfunction "5_5") (pintype "passive"))
      (node (ref "TETHER") (pin "6") (pinfunction "6_6") (pintype "passive"))
    )
    (net (code "23") (name "LED_DRIVE_A") (class "Default")
      (node (ref "D5") (pin "A") (pinfunction "A_A") (pintype "passive"))
      (node (ref "Q5") (pin "1") (pinfunction "G_1") (pintype "bidirectional"))
      (node (ref "R8") (pin "2") (pinfunction "2_2") (pintype "passive"))
    )
    (net (code "24") (name "LED_DRIVE_B") (class "Default")
      (node (ref "D7") (pin "A") (pinfunction "A_A") (pintype "passive"))
      (node (ref "Q6") (pin "1") (pinfunction "G_1") (pintype "bidirectional"))
      (node (ref "R10") (pin "2") (pinfunction "2_2") (pintype "passive"))
    )
    (net (code "25") (name "Net-(D2-PadA)") (class "Default")
      (node (ref "D2") (pin "A") (pinfunction "A_A") (pintype "passive"))
      (node (ref "D3") (pin "C") (pinfunction "C_C") (pintype "passive"))
    )
    (net (code "26") (name "Net-(D6-PadC)") (class "Default")
      (node (ref "D6") (pin "C") (pinfunction "C_C") (pintype "passive"))
      (node (ref "R9") (pin "1") (pinfunction "1_1") (pintype "passive"))
    )
    (net (code "27") (name "Net-(D8-PadC)") (class "Default")
      (node (ref "D8") (pin "C") (pinfunction "C_C") (pintype "passive"))
      (node (ref "R11") (pin "1") (pinfunction "1_1") (pintype "passive"))
    )
    (net (code "28") (name "Net-(Q5-D)") (class "Default")
      (node (ref "Q5") (pin "3") (pinfunction "D_3") (pintype "bidirectional"))
      (node (ref "R9") (pin "2") (pinfunction "2_2") (pintype "passive"))
    )
    (net (code "29") (name "Net-(Q6-D)") (class "Default")
      (node (ref "Q6") (pin "3") (pinfunction "D_3") (pintype "bidirectional"))
      (node (ref "R11") (pin "2") (pinfunction "2_2") (pintype "passive"))
    )
    (net (code "30") (name "ON{slash}OFF") (class "Default")
      (node (ref "BRICK1") (pin "B") (pinfunction "ON/OFF_B") (pintype "bidirectional"))
      (node (ref "BRICK2") (pin "B") (pinfunction "ON/OFF_B") (pintype "bidirectional"))
      (node (ref "D4") (pin "C") (pinfunction "C_C") (pintype "passive"))
      (node (ref "Q2") (pin "3") (pinfunction "D_3") (pintype "bidirectional"))
      (node (ref "R3") (pin "1") (pinfunction "1_1") (pintype "passive"))
    )
    (net (code "31") (name "OR_DRIVE_A") (class "Default")
      (node (ref "D5") (pin "C") (pinfunction "C_C") (pintype "passive"))
      (node (ref "Q3") (pin "1") (pinfunction "G_1") (pintype "bidirectional"))
      (node (ref "U1") (pin "2") (pinfunction "GATE_PULL_DOWN_2") (pintype "passive"))
      (node (ref "U1") (pin "6") (pinfunction "GATE_DRIVE_6") (pintype "output"))
      (node (ref "U3") (pin "5") (pinfunction "GATE_5") (pintype "passive"))
    )
    (net (code "32") (name "OR_DRIVE_B") (class "Default")
      (node (ref "D7") (pin "C") (pinfunction "C_C") (pintype "passive"))
      (node (ref "Q4") (pin "1") (pinfunction "G_1") (pintype "bidirectional"))
      (node (ref "U2") (pin "2") (pinfunction "GATE_PULL_DOWN_2") (pintype "passive"))
      (node (ref "U2") (pin "6") (pinfunction "GATE_DRIVE_6") (pintype "output"))
      (node (ref "U4") (pin "5") (pinfunction "GATE_5") (pintype "passive"))
    )
    (net (code "33") (name "unconnected-(U1-NC-Pad5)") (class "Default")
      (node (ref "U1") (pin "5") (pinfunction "NC_5") (pintype "passive"))
    )
    (net (code "34") (name "unconnected-(U1-NC_2-Pad3)") (class "Default")
      (node (ref "U1") (pin "3") (pinfunction "NC_2_3") (pintype "passive"))
    )
    (net (code "35") (name "unconnected-(U2-NC-Pad5)") (class "Default")
      (node (ref "U2") (pin "5") (pinfunction "NC_5") (pintype "passive"))
    )
    (net (code "36") (name "unconnected-(U2-NC_2-Pad3)") (class "Default")
      (node (ref "U2") (pin "3") (pinfunction "NC_2_3") (pintype "passive"))
    )
    (net (code "37") (name "unconnected-(U3-OFF-Pad3)") (class "Default")
      (node (ref "U3") (pin "3") (pinfunction "OFF_3") (pintype "passive"))
    )
    (net (code "38") (name "unconnected-(U4-OFF-Pad3)") (class "Default")
      (node (ref "U4") (pin "3") (pinfunction "OFF_3") (pintype "passive"))
    )
  )
)
